# Cont.net
KiCad netlist of a schematic drawn in EAGLE
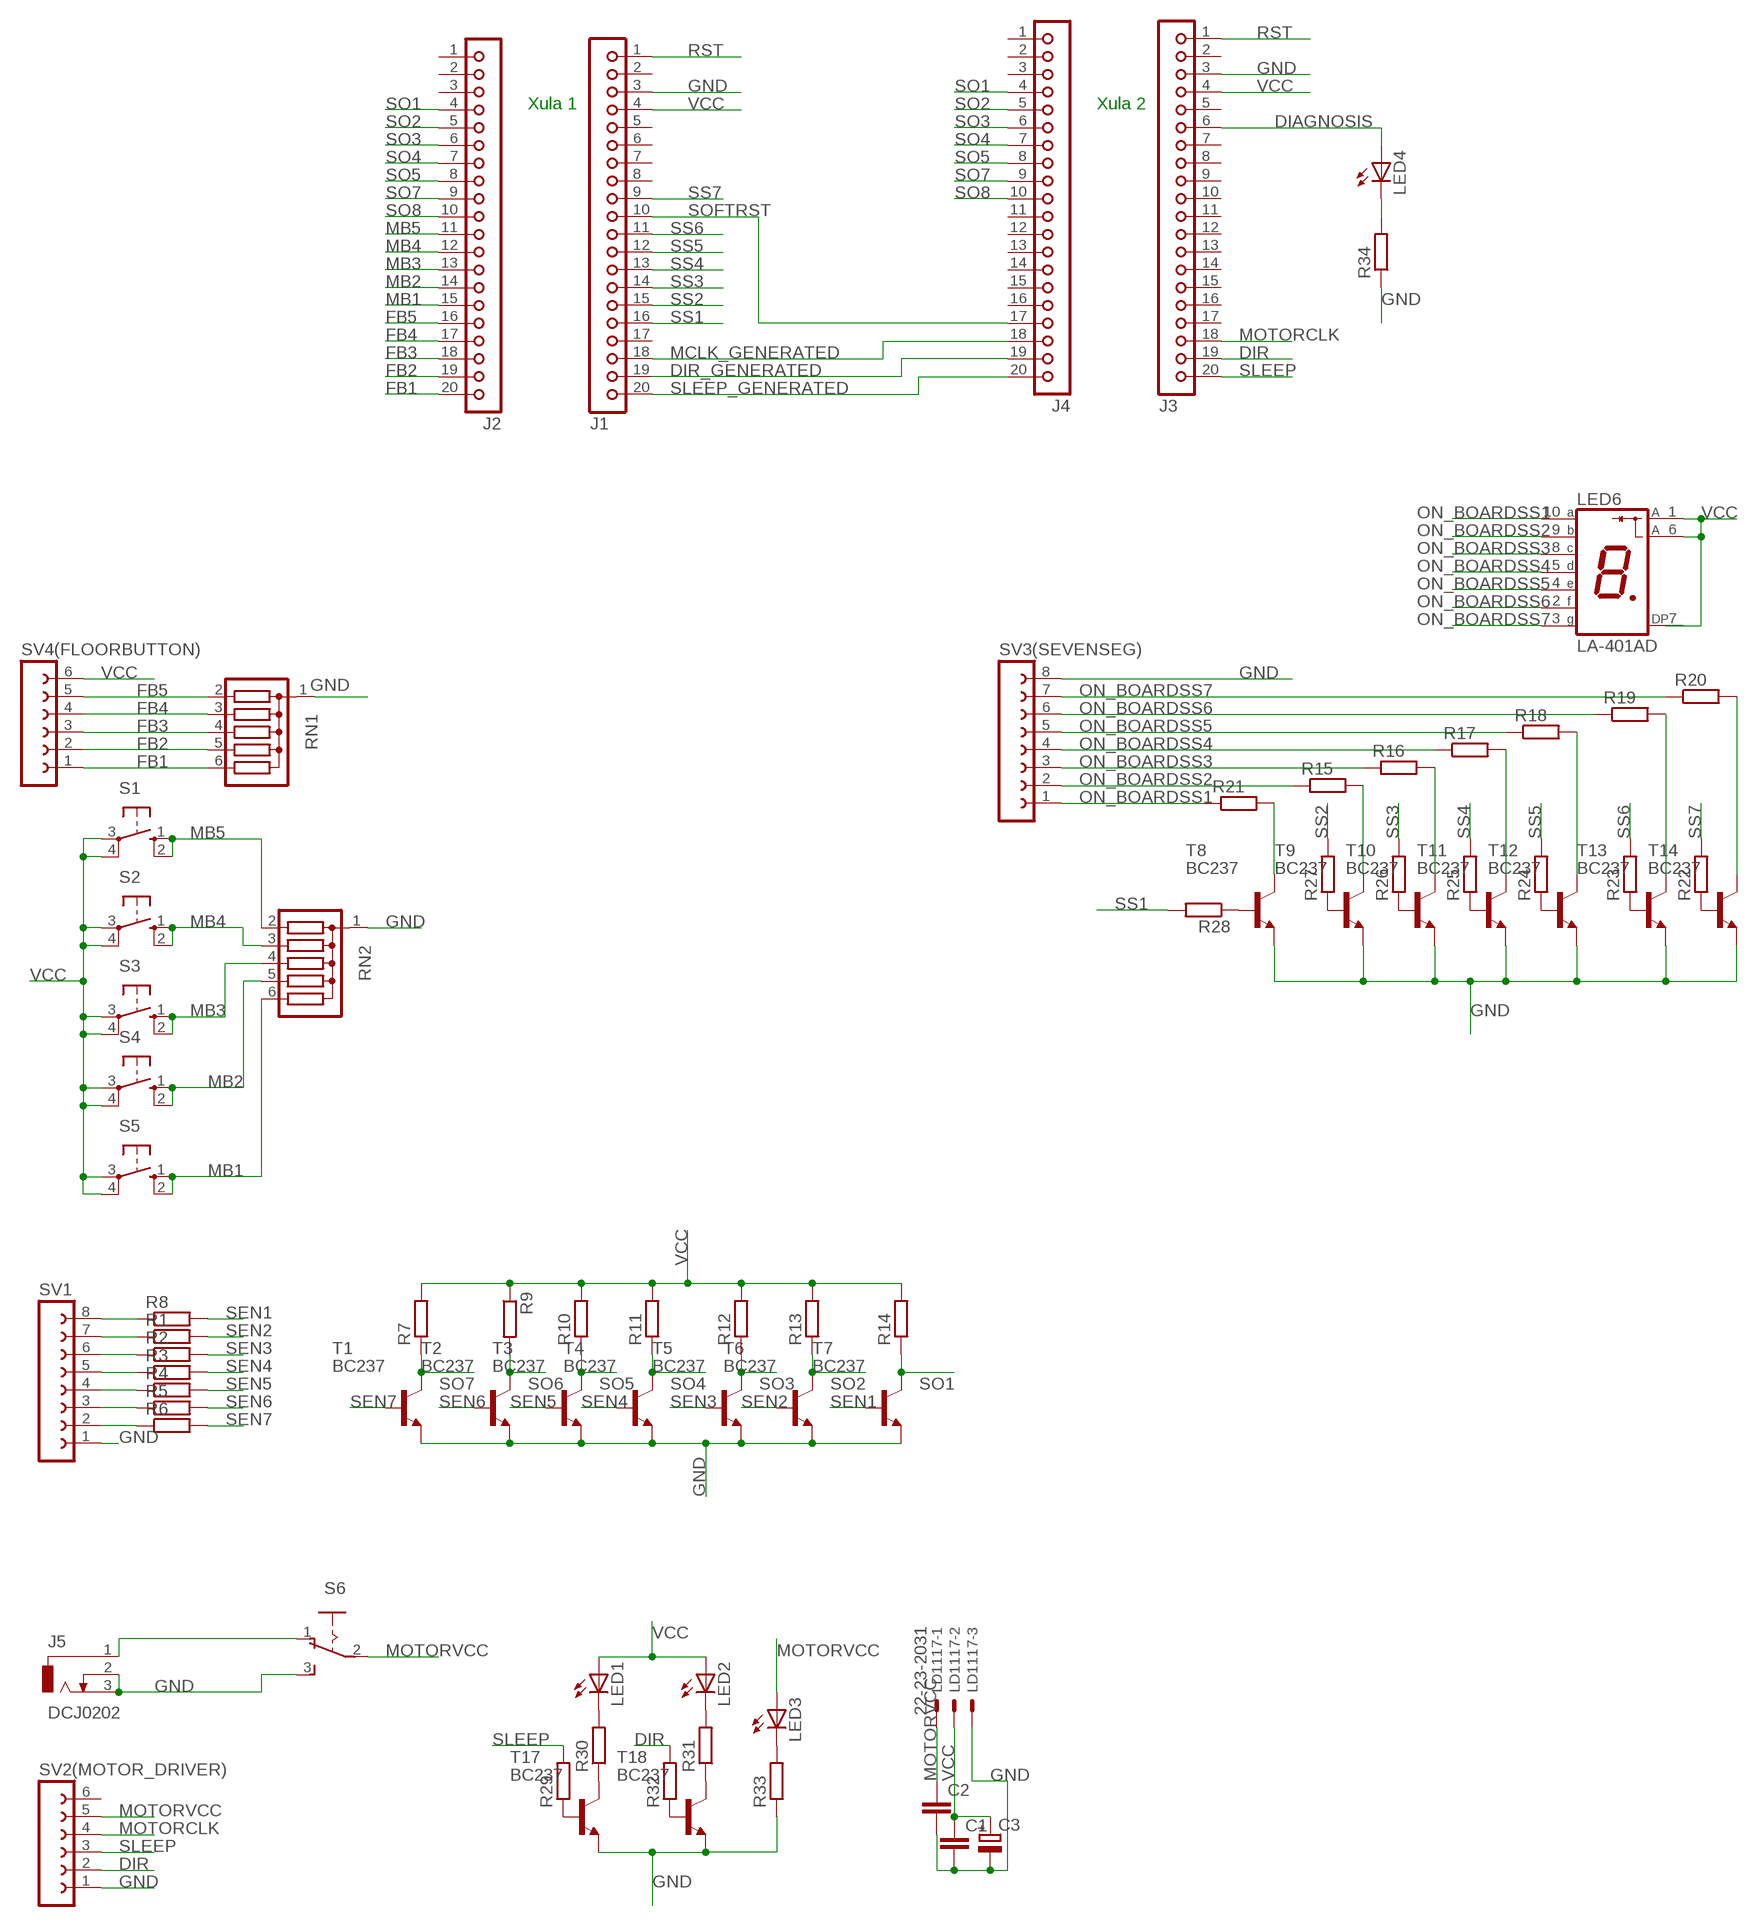
[diagram p0: schematic, sheet 1]

(export (version "E")
  (design (tool "Eeschema 10.0.6"))
  (components
    (comp (ref "C1")
      (value "C-EU025-025X050")
      (footprint "eagle-import:C025-025X050")
      (libsource (lib "eagle-import") (part "C-EU025-025X050"))
    )
    (comp (ref "C2")
      (value "C-EU025-025X050")
      (footprint "eagle-import:C025-025X050")
      (libsource (lib "eagle-import") (part "C-EU025-025X050"))
    )
    (comp (ref "C3")
      (value "CPOL-EUE3.5-8")
      (footprint "eagle-import:E3,5-8")
      (libsource (lib "eagle-import") (part "CPOL-EUE3.5-8"))
    )
    (comp (ref "J1")
      (value "JBK20")
      (footprint "eagle-import:JBK20")
      (libsource (lib "eagle-import") (part "JBK20"))
    )
    (comp (ref "J2")
      (value "JBK20")
      (footprint "eagle-import:JBK20")
      (libsource (lib "eagle-import") (part "JBK20"))
    )
    (comp (ref "J3")
      (value "JBK20")
      (footprint "eagle-import:JBK20")
      (libsource (lib "eagle-import") (part "JBK20"))
    )
    (comp (ref "J4")
      (value "JBK20")
      (footprint "eagle-import:JBK20")
      (libsource (lib "eagle-import") (part "JBK20"))
    )
    (comp (ref "J5")
      (value "DCJ0202")
      (footprint "eagle-import:DCJ0202")
      (libsource (lib "eagle-import") (part "DCJ0202"))
    )
    (comp (ref "LD1117")
      (value "22-23-2031")
      (footprint "eagle-import:22-23-2031")
      (fields (field (name "MF") "MOLEX"))
      (libsource (lib "eagle-import") (part "22-23-2031"))
    )
    (comp (ref "LED1")
      (value "LED3MM")
      (footprint "eagle-import:LED3MM")
      (libsource (lib "eagle-import") (part "LED3MM"))
    )
    (comp (ref "LED2")
      (value "LED3MM")
      (footprint "eagle-import:LED3MM")
      (libsource (lib "eagle-import") (part "LED3MM"))
    )
    (comp (ref "LED3")
      (value "LED3MM")
      (footprint "eagle-import:LED3MM")
      (libsource (lib "eagle-import") (part "LED3MM"))
    )
    (comp (ref "LED4")
      (value "LED3MM")
      (footprint "eagle-import:LED3MM")
      (libsource (lib "eagle-import") (part "LED3MM"))
    )
    (comp (ref "LED6")
      (value "LA-401AD")
      (footprint "eagle-import:LA-401")
      (libsource (lib "eagle-import") (part "LA-401DA"))
    )
    (comp (ref "R1")
      (value "R-EU_0204/5")
      (footprint "eagle-import:0204_5")
      (libsource (lib "eagle-import") (part "R-EU_0204/5"))
    )
    (comp (ref "R2")
      (value "R-EU_0204/5")
      (footprint "eagle-import:0204_5")
      (libsource (lib "eagle-import") (part "R-EU_0204/5"))
    )
    (comp (ref "R3")
      (value "R-EU_0204/5")
      (footprint "eagle-import:0204_5")
      (libsource (lib "eagle-import") (part "R-EU_0204/5"))
    )
    (comp (ref "R4")
      (value "R-EU_0204/5")
      (footprint "eagle-import:0204_5")
      (libsource (lib "eagle-import") (part "R-EU_0204/5"))
    )
    (comp (ref "R5")
      (value "R-EU_0204/5")
      (footprint "eagle-import:0204_5")
      (libsource (lib "eagle-import") (part "R-EU_0204/5"))
    )
    (comp (ref "R6")
      (value "R-EU_0204/5")
      (footprint "eagle-import:0204_5")
      (libsource (lib "eagle-import") (part "R-EU_0204/5"))
    )
    (comp (ref "R7")
      (value "R-EU_0204/5")
      (footprint "eagle-import:0204_5")
      (libsource (lib "eagle-import") (part "R-EU_0204/5"))
    )
    (comp (ref "R8")
      (value "R-EU_0204/5")
      (footprint "eagle-import:0204_5")
      (libsource (lib "eagle-import") (part "R-EU_0204/5"))
    )
    (comp (ref "R9")
      (value "R-EU_0204/5")
      (footprint "eagle-import:0204_5")
      (libsource (lib "eagle-import") (part "R-EU_0204/5"))
    )
    (comp (ref "R10")
      (value "R-EU_0204/5")
      (footprint "eagle-import:0204_5")
      (libsource (lib "eagle-import") (part "R-EU_0204/5"))
    )
    (comp (ref "R11")
      (value "R-EU_0204/5")
      (footprint "eagle-import:0204_5")
      (libsource (lib "eagle-import") (part "R-EU_0204/5"))
    )
    (comp (ref "R12")
      (value "R-EU_0204/5")
      (footprint "eagle-import:0204_5")
      (libsource (lib "eagle-import") (part "R-EU_0204/5"))
    )
    (comp (ref "R13")
      (value "R-EU_0204/5")
      (footprint "eagle-import:0204_5")
      (libsource (lib "eagle-import") (part "R-EU_0204/5"))
    )
    (comp (ref "R14")
      (value "R-EU_0204/5")
      (footprint "eagle-import:0204_5")
      (libsource (lib "eagle-import") (part "R-EU_0204/5"))
    )
    (comp (ref "R15")
      (value "R-EU_0204/5")
      (footprint "eagle-import:0204_5")
      (libsource (lib "eagle-import") (part "R-EU_0204/5"))
    )
    (comp (ref "R16")
      (value "R-EU_0204/5")
      (footprint "eagle-import:0204_5")
      (libsource (lib "eagle-import") (part "R-EU_0204/5"))
    )
    (comp (ref "R17")
      (value "R-EU_0204/5")
      (footprint "eagle-import:0204_5")
      (libsource (lib "eagle-import") (part "R-EU_0204/5"))
    )
    (comp (ref "R18")
      (value "R-EU_0204/5")
      (footprint "eagle-import:0204_5")
      (libsource (lib "eagle-import") (part "R-EU_0204/5"))
    )
    (comp (ref "R19")
      (value "R-EU_0204/5")
      (footprint "eagle-import:0204_5")
      (libsource (lib "eagle-import") (part "R-EU_0204/5"))
    )
    (comp (ref "R20")
      (value "R-EU_0204/5")
      (footprint "eagle-import:0204_5")
      (libsource (lib "eagle-import") (part "R-EU_0204/5"))
    )
    (comp (ref "R21")
      (value "R-EU_0204/5")
      (footprint "eagle-import:0204_5")
      (libsource (lib "eagle-import") (part "R-EU_0204/5"))
    )
    (comp (ref "R22")
      (value "R-EU_0204/5")
      (footprint "eagle-import:0204_5")
      (libsource (lib "eagle-import") (part "R-EU_0204/5"))
    )
    (comp (ref "R23")
      (value "R-EU_0204/5")
      (footprint "eagle-import:0204_5")
      (libsource (lib "eagle-import") (part "R-EU_0204/5"))
    )
    (comp (ref "R24")
      (value "R-EU_0204/5")
      (footprint "eagle-import:0204_5")
      (libsource (lib "eagle-import") (part "R-EU_0204/5"))
    )
    (comp (ref "R25")
      (value "R-EU_0204/5")
      (footprint "eagle-import:0204_5")
      (libsource (lib "eagle-import") (part "R-EU_0204/5"))
    )
    (comp (ref "R26")
      (value "R-EU_0204/5")
      (footprint "eagle-import:0204_5")
      (libsource (lib "eagle-import") (part "R-EU_0204/5"))
    )
    (comp (ref "R27")
      (value "R-EU_0204/5")
      (footprint "eagle-import:0204_5")
      (libsource (lib "eagle-import") (part "R-EU_0204/5"))
    )
    (comp (ref "R28")
      (value "R-EU_0204/5")
      (footprint "eagle-import:0204_5")
      (libsource (lib "eagle-import") (part "R-EU_0204/5"))
    )
    (comp (ref "R29")
      (value "R-EU_0204/5")
      (footprint "eagle-import:0204_5")
      (libsource (lib "eagle-import") (part "R-EU_0204/5"))
    )
    (comp (ref "R30")
      (value "R-EU_0204/5")
      (footprint "eagle-import:0204_5")
      (libsource (lib "eagle-import") (part "R-EU_0204/5"))
    )
    (comp (ref "R31")
      (value "R-EU_0204/5")
      (footprint "eagle-import:0204_5")
      (libsource (lib "eagle-import") (part "R-EU_0204/5"))
    )
    (comp (ref "R32")
      (value "R-EU_0204/5")
      (footprint "eagle-import:0204_5")
      (libsource (lib "eagle-import") (part "R-EU_0204/5"))
    )
    (comp (ref "R33")
      (value "R-EU_0204/5")
      (footprint "eagle-import:0204_5")
      (libsource (lib "eagle-import") (part "R-EU_0204/5"))
    )
    (comp (ref "R34")
      (value "R-EU_0204/5")
      (footprint "eagle-import:0204_5")
      (libsource (lib "eagle-import") (part "R-EU_0204/5"))
    )
    (comp (ref "RN1")
      (value "G05R")
      (footprint "eagle-import:SIL6")
      (libsource (lib "eagle-import") (part "G05R"))
    )
    (comp (ref "RN2")
      (value "G05R")
      (footprint "eagle-import:SIL6")
      (libsource (lib "eagle-import") (part "G05R"))
    )
    (comp (ref "S1")
      (value "10-XX")
      (footprint "eagle-import:B3F-10XX")
      (fields (field (name "MPN") "B3F-1000"))
      (libsource (lib "eagle-import") (part "10-XX"))
    )
    (comp (ref "S2")
      (value "10-XX")
      (footprint "eagle-import:B3F-10XX")
      (fields (field (name "MPN") "B3F-1000"))
      (libsource (lib "eagle-import") (part "10-XX"))
    )
    (comp (ref "S3")
      (value "10-XX")
      (footprint "eagle-import:B3F-10XX")
      (fields (field (name "MPN") "B3F-1000"))
      (libsource (lib "eagle-import") (part "10-XX"))
    )
    (comp (ref "S4")
      (value "10-XX")
      (footprint "eagle-import:B3F-10XX")
      (fields (field (name "MPN") "B3F-1000"))
      (libsource (lib "eagle-import") (part "10-XX"))
    )
    (comp (ref "S5")
      (value "10-XX")
      (footprint "eagle-import:B3F-10XX")
      (fields (field (name "MPN") "B3F-1000"))
      (libsource (lib "eagle-import") (part "10-XX"))
    )
    (comp (ref "S6")
      (value "255SB")
      (footprint "eagle-import:255SB")
      (libsource (lib "eagle-import") (part "255SB"))
    )
    (comp (ref "SV1")
      (value "FE08-1")
      (footprint "eagle-import:FE08")
      (libsource (lib "eagle-import") (part "FE08-1"))
    )
    (comp (ref "SV2(MOTOR_DRIVER)")
      (value "FE06-1")
      (footprint "eagle-import:FE06")
      (libsource (lib "eagle-import") (part "FE06-1"))
    )
    (comp (ref "SV3(SEVENSEG)")
      (value "FE08W")
      (footprint "eagle-import:FE08W")
      (libsource (lib "eagle-import") (part "FE08W"))
    )
    (comp (ref "SV4(FLOORBUTTON)")
      (value "FE06-1")
      (footprint "eagle-import:FE06")
      (libsource (lib "eagle-import") (part "FE06-1"))
    )
    (comp (ref "T1")
      (value "BC237")
      (footprint "eagle-import:TO92")
      (libsource (lib "eagle-import") (part "BC237"))
    )
    (comp (ref "T2")
      (value "BC237")
      (footprint "eagle-import:TO92")
      (libsource (lib "eagle-import") (part "BC237"))
    )
    (comp (ref "T3")
      (value "BC237")
      (footprint "eagle-import:TO92")
      (libsource (lib "eagle-import") (part "BC237"))
    )
    (comp (ref "T4")
      (value "BC237")
      (footprint "eagle-import:TO92")
      (libsource (lib "eagle-import") (part "BC237"))
    )
    (comp (ref "T5")
      (value "BC237")
      (footprint "eagle-import:TO92")
      (libsource (lib "eagle-import") (part "BC237"))
    )
    (comp (ref "T6")
      (value "BC237")
      (footprint "eagle-import:TO92")
      (libsource (lib "eagle-import") (part "BC237"))
    )
    (comp (ref "T7")
      (value "BC237")
      (footprint "eagle-import:TO92")
      (libsource (lib "eagle-import") (part "BC237"))
    )
    (comp (ref "T8")
      (value "BC237")
      (footprint "eagle-import:TO92")
      (libsource (lib "eagle-import") (part "BC237"))
    )
    (comp (ref "T9")
      (value "BC237")
      (footprint "eagle-import:TO92")
      (libsource (lib "eagle-import") (part "BC237"))
    )
    (comp (ref "T10")
      (value "BC237")
      (footprint "eagle-import:TO92")
      (libsource (lib "eagle-import") (part "BC237"))
    )
    (comp (ref "T11")
      (value "BC237")
      (footprint "eagle-import:TO92")
      (libsource (lib "eagle-import") (part "BC237"))
    )
    (comp (ref "T12")
      (value "BC237")
      (footprint "eagle-import:TO92")
      (libsource (lib "eagle-import") (part "BC237"))
    )
    (comp (ref "T13")
      (value "BC237")
      (footprint "eagle-import:TO92")
      (libsource (lib "eagle-import") (part "BC237"))
    )
    (comp (ref "T14")
      (value "BC237")
      (footprint "eagle-import:TO92")
      (libsource (lib "eagle-import") (part "BC237"))
    )
    (comp (ref "T17")
      (value "BC237")
      (footprint "eagle-import:TO92")
      (libsource (lib "eagle-import") (part "BC237"))
    )
    (comp (ref "T18")
      (value "BC237")
      (footprint "eagle-import:TO92")
      (libsource (lib "eagle-import") (part "BC237"))
    )
  )
  (nets
    (net (code "1") (name "/DIAGNOSIS") (class "Default")
      (node (ref "J3") (pin "6") (pinfunction "6_6") (pintype "passive"))
      (node (ref "LED4") (pin "A") (pinfunction "A_A") (pintype "passive"))
    )
    (net (code "2") (name "/DIR") (class "Default")
      (node (ref "J3") (pin "19") (pinfunction "19_19") (pintype "passive"))
      (node (ref "R32") (pin "2") (pinfunction "2_2") (pintype "passive"))
      (node (ref "SV2(MOTOR_DRIVER)") (pin "2") (pinfunction "2_2") (pintype "passive"))
    )
    (net (code "3") (name "/DIR_GENERATED") (class "Default")
      (node (ref "J1") (pin "19") (pinfunction "19_19") (pintype "passive"))
      (node (ref "J4") (pin "19") (pinfunction "19_19") (pintype "passive"))
    )
    (net (code "4") (name "/FB1") (class "Default")
      (node (ref "J2") (pin "20") (pinfunction "20_20") (pintype "passive"))
      (node (ref "RN1") (pin "6") (pinfunction "6_6") (pintype "passive"))
      (node (ref "SV4(FLOORBUTTON)") (pin "1") (pinfunction "1_1") (pintype "passive"))
    )
    (net (code "5") (name "/FB2") (class "Default")
      (node (ref "J2") (pin "19") (pinfunction "19_19") (pintype "passive"))
      (node (ref "RN1") (pin "5") (pinfunction "5_5") (pintype "passive"))
      (node (ref "SV4(FLOORBUTTON)") (pin "2") (pinfunction "2_2") (pintype "passive"))
    )
    (net (code "6") (name "/FB3") (class "Default")
      (node (ref "J2") (pin "18") (pinfunction "18_18") (pintype "passive"))
      (node (ref "RN1") (pin "4") (pinfunction "4_4") (pintype "passive"))
      (node (ref "SV4(FLOORBUTTON)") (pin "3") (pinfunction "3_3") (pintype "passive"))
    )
    (net (code "7") (name "/FB4") (class "Default")
      (node (ref "J2") (pin "17") (pinfunction "17_17") (pintype "passive"))
      (node (ref "RN1") (pin "3") (pinfunction "3_3") (pintype "passive"))
      (node (ref "SV4(FLOORBUTTON)") (pin "4") (pinfunction "4_4") (pintype "passive"))
    )
    (net (code "8") (name "/FB5") (class "Default")
      (node (ref "J2") (pin "16") (pinfunction "16_16") (pintype "passive"))
      (node (ref "RN1") (pin "2") (pinfunction "2_2") (pintype "passive"))
      (node (ref "SV4(FLOORBUTTON)") (pin "5") (pinfunction "5_5") (pintype "passive"))
    )
    (net (code "9") (name "/GND") (class "Default")
      (node (ref "C1") (pin "2") (pinfunction "2_2") (pintype "passive"))
      (node (ref "C2") (pin "2") (pinfunction "2_2") (pintype "passive"))
      (node (ref "C3") (pin "-") (pinfunction "-_-") (pintype "passive"))
      (node (ref "J1") (pin "3") (pinfunction "3_3") (pintype "passive"))
      (node (ref "J3") (pin "3") (pinfunction "3_3") (pintype "passive"))
      (node (ref "J5") (pin "2") (pinfunction "2_2") (pintype "passive"))
      (node (ref "J5") (pin "3") (pinfunction "3_3") (pintype "passive"))
      (node (ref "LD1117") (pin "3") (pinfunction "S_3") (pintype "passive"))
      (node (ref "R33") (pin "1") (pinfunction "1_1") (pintype "passive"))
      (node (ref "R34") (pin "1") (pinfunction "1_1") (pintype "passive"))
      (node (ref "R6") (pin "1") (pinfunction "1_1") (pintype "passive"))
      (node (ref "RN1") (pin "1") (pinfunction "1_1") (pintype "passive"))
      (node (ref "RN2") (pin "1") (pinfunction "1_1") (pintype "passive"))
      (node (ref "S6") (pin "3") (pinfunction "S_3") (pintype "passive"))
      (node (ref "SV1") (pin "1") (pinfunction "1_1") (pintype "passive"))
      (node (ref "SV1") (pin "2") (pinfunction "2_2") (pintype "passive"))
      (node (ref "SV2(MOTOR_DRIVER)") (pin "1") (pinfunction "1_1") (pintype "passive"))
      (node (ref "SV3(SEVENSEG)") (pin "8") (pinfunction "8_8") (pintype "passive"))
      (node (ref "T1") (pin "1") (pinfunction "E_1") (pintype "passive"))
      (node (ref "T10") (pin "1") (pinfunction "E_1") (pintype "passive"))
      (node (ref "T11") (pin "1") (pinfunction "E_1") (pintype "passive"))
      (node (ref "T12") (pin "1") (pinfunction "E_1") (pintype "passive"))
      (node (ref "T13") (pin "1") (pinfunction "E_1") (pintype "passive"))
      (node (ref "T14") (pin "1") (pinfunction "E_1") (pintype "passive"))
      (node (ref "T17") (pin "1") (pinfunction "E_1") (pintype "passive"))
      (node (ref "T18") (pin "1") (pinfunction "E_1") (pintype "passive"))
      (node (ref "T2") (pin "1") (pinfunction "E_1") (pintype "passive"))
      (node (ref "T3") (pin "1") (pinfunction "E_1") (pintype "passive"))
      (node (ref "T4") (pin "1") (pinfunction "E_1") (pintype "passive"))
      (node (ref "T5") (pin "1") (pinfunction "E_1") (pintype "passive"))
      (node (ref "T6") (pin "1") (pinfunction "E_1") (pintype "passive"))
      (node (ref "T7") (pin "1") (pinfunction "E_1") (pintype "passive"))
      (node (ref "T8") (pin "1") (pinfunction "E_1") (pintype "passive"))
      (node (ref "T9") (pin "1") (pinfunction "E_1") (pintype "passive"))
    )
    (net (code "10") (name "/MB1") (class "Default")
      (node (ref "J2") (pin "15") (pinfunction "15_15") (pintype "passive"))
      (node (ref "RN2") (pin "6") (pinfunction "6_6") (pintype "passive"))
      (node (ref "S5") (pin "1") (pinfunction "S_1") (pintype "passive"))
      (node (ref "S5") (pin "2") (pinfunction "S1_2") (pintype "passive"))
    )
    (net (code "11") (name "/MB2") (class "Default")
      (node (ref "J2") (pin "14") (pinfunction "14_14") (pintype "passive"))
      (node (ref "RN2") (pin "5") (pinfunction "5_5") (pintype "passive"))
      (node (ref "S4") (pin "1") (pinfunction "S_1") (pintype "passive"))
      (node (ref "S4") (pin "2") (pinfunction "S1_2") (pintype "passive"))
    )
    (net (code "12") (name "/MB3") (class "Default")
      (node (ref "J2") (pin "13") (pinfunction "13_13") (pintype "passive"))
      (node (ref "RN2") (pin "4") (pinfunction "4_4") (pintype "passive"))
      (node (ref "S3") (pin "1") (pinfunction "S_1") (pintype "passive"))
      (node (ref "S3") (pin "2") (pinfunction "S1_2") (pintype "passive"))
    )
    (net (code "13") (name "/MB4") (class "Default")
      (node (ref "J2") (pin "12") (pinfunction "12_12") (pintype "passive"))
      (node (ref "RN2") (pin "3") (pinfunction "3_3") (pintype "passive"))
      (node (ref "S2") (pin "1") (pinfunction "S_1") (pintype "passive"))
      (node (ref "S2") (pin "2") (pinfunction "S1_2") (pintype "passive"))
    )
    (net (code "14") (name "/MB5") (class "Default")
      (node (ref "J2") (pin "11") (pinfunction "11_11") (pintype "passive"))
      (node (ref "RN2") (pin "2") (pinfunction "2_2") (pintype "passive"))
      (node (ref "S1") (pin "1") (pinfunction "S_1") (pintype "passive"))
      (node (ref "S1") (pin "2") (pinfunction "S1_2") (pintype "passive"))
    )
    (net (code "15") (name "/MCLK_GENERATED") (class "Default")
      (node (ref "J1") (pin "18") (pinfunction "18_18") (pintype "passive"))
      (node (ref "J4") (pin "18") (pinfunction "18_18") (pintype "passive"))
    )
    (net (code "16") (name "/MOTORCLK") (class "Default")
      (node (ref "J3") (pin "18") (pinfunction "18_18") (pintype "passive"))
      (node (ref "SV2(MOTOR_DRIVER)") (pin "4") (pinfunction "4_4") (pintype "passive"))
    )
    (net (code "17") (name "/MOTORVCC") (class "Default")
      (node (ref "C2") (pin "1") (pinfunction "1_1") (pintype "passive"))
      (node (ref "LD1117") (pin "1") (pinfunction "S_1") (pintype "passive"))
      (node (ref "LED3") (pin "A") (pinfunction "A_A") (pintype "passive"))
      (node (ref "S6") (pin "2") (pinfunction "P_2") (pintype "passive"))
      (node (ref "SV2(MOTOR_DRIVER)") (pin "5") (pinfunction "5_5") (pintype "passive"))
    )
    (net (code "18") (name "/ON_BOARDSS1") (class "Default")
      (node (ref "LED6") (pin "10") (pinfunction "A_10") (pintype "passive"))
      (node (ref "R21") (pin "1") (pinfunction "1_1") (pintype "passive"))
      (node (ref "SV3(SEVENSEG)") (pin "1") (pinfunction "1_1") (pintype "passive"))
    )
    (net (code "19") (name "/ON_BOARDSS2") (class "Default")
      (node (ref "LED6") (pin "9") (pinfunction "B_9") (pintype "passive"))
      (node (ref "R15") (pin "1") (pinfunction "1_1") (pintype "passive"))
      (node (ref "SV3(SEVENSEG)") (pin "2") (pinfunction "2_2") (pintype "passive"))
    )
    (net (code "20") (name "/ON_BOARDSS3") (class "Default")
      (node (ref "LED6") (pin "8") (pinfunction "C_8") (pintype "passive"))
      (node (ref "R16") (pin "1") (pinfunction "1_1") (pintype "passive"))
      (node (ref "SV3(SEVENSEG)") (pin "3") (pinfunction "3_3") (pintype "passive"))
    )
    (net (code "21") (name "/ON_BOARDSS4") (class "Default")
      (node (ref "LED6") (pin "5") (pinfunction "D_5") (pintype "passive"))
      (node (ref "R17") (pin "1") (pinfunction "1_1") (pintype "passive"))
      (node (ref "SV3(SEVENSEG)") (pin "4") (pinfunction "4_4") (pintype "passive"))
    )
    (net (code "22") (name "/ON_BOARDSS5") (class "Default")
      (node (ref "LED6") (pin "4") (pinfunction "E_4") (pintype "passive"))
      (node (ref "R18") (pin "1") (pinfunction "1_1") (pintype "passive"))
      (node (ref "SV3(SEVENSEG)") (pin "5") (pinfunction "5_5") (pintype "passive"))
    )
    (net (code "23") (name "/ON_BOARDSS6") (class "Default")
      (node (ref "LED6") (pin "2") (pinfunction "F_2") (pintype "passive"))
      (node (ref "R19") (pin "1") (pinfunction "1_1") (pintype "passive"))
      (node (ref "SV3(SEVENSEG)") (pin "6") (pinfunction "6_6") (pintype "passive"))
    )
    (net (code "24") (name "/ON_BOARDSS7") (class "Default")
      (node (ref "LED6") (pin "3") (pinfunction "G_3") (pintype "passive"))
      (node (ref "R20") (pin "1") (pinfunction "1_1") (pintype "passive"))
      (node (ref "SV3(SEVENSEG)") (pin "7") (pinfunction "7_7") (pintype "passive"))
    )
    (net (code "25") (name "/RST") (class "Default")
      (node (ref "J1") (pin "1") (pinfunction "1_1") (pintype "passive"))
      (node (ref "J3") (pin "1") (pinfunction "1_1") (pintype "passive"))
    )
    (net (code "26") (name "/SEN1") (class "Default")
      (node (ref "R8") (pin "2") (pinfunction "2_2") (pintype "passive"))
      (node (ref "T7") (pin "2") (pinfunction "B_2") (pintype "passive"))
    )
    (net (code "27") (name "/SEN2") (class "Default")
      (node (ref "R1") (pin "2") (pinfunction "2_2") (pintype "passive"))
      (node (ref "T6") (pin "2") (pinfunction "B_2") (pintype "passive"))
    )
    (net (code "28") (name "/SEN3") (class "Default")
      (node (ref "R2") (pin "2") (pinfunction "2_2") (pintype "passive"))
      (node (ref "T5") (pin "2") (pinfunction "B_2") (pintype "passive"))
    )
    (net (code "29") (name "/SEN4") (class "Default")
      (node (ref "R3") (pin "2") (pinfunction "2_2") (pintype "passive"))
      (node (ref "T4") (pin "2") (pinfunction "B_2") (pintype "passive"))
    )
    (net (code "30") (name "/SEN5") (class "Default")
      (node (ref "R4") (pin "2") (pinfunction "2_2") (pintype "passive"))
      (node (ref "T3") (pin "2") (pinfunction "B_2") (pintype "passive"))
    )
    (net (code "31") (name "/SEN6") (class "Default")
      (node (ref "R5") (pin "2") (pinfunction "2_2") (pintype "passive"))
      (node (ref "T2") (pin "2") (pinfunction "B_2") (pintype "passive"))
    )
    (net (code "32") (name "/SEN7") (class "Default")
      (node (ref "R6") (pin "2") (pinfunction "2_2") (pintype "passive"))
      (node (ref "T1") (pin "2") (pinfunction "B_2") (pintype "passive"))
    )
    (net (code "33") (name "/SLEEP") (class "Default")
      (node (ref "J3") (pin "20") (pinfunction "20_20") (pintype "passive"))
      (node (ref "R29") (pin "2") (pinfunction "2_2") (pintype "passive"))
      (node (ref "SV2(MOTOR_DRIVER)") (pin "3") (pinfunction "3_3") (pintype "passive"))
    )
    (net (code "34") (name "/SLEEP_GENERATED") (class "Default")
      (node (ref "J1") (pin "20") (pinfunction "20_20") (pintype "passive"))
      (node (ref "J4") (pin "20") (pinfunction "20_20") (pintype "passive"))
    )
    (net (code "35") (name "/SO1") (class "Default")
      (node (ref "J2") (pin "4") (pinfunction "4_4") (pintype "passive"))
      (node (ref "J4") (pin "4") (pinfunction "4_4") (pintype "passive"))
      (node (ref "R14") (pin "1") (pinfunction "1_1") (pintype "passive"))
      (node (ref "T7") (pin "3") (pinfunction "C_3") (pintype "passive"))
    )
    (net (code "36") (name "/SO2") (class "Default")
      (node (ref "J2") (pin "5") (pinfunction "5_5") (pintype "passive"))
      (node (ref "J4") (pin "5") (pinfunction "5_5") (pintype "passive"))
      (node (ref "R13") (pin "1") (pinfunction "1_1") (pintype "passive"))
      (node (ref "T6") (pin "3") (pinfunction "C_3") (pintype "passive"))
    )
    (net (code "37") (name "/SO3") (class "Default")
      (node (ref "J2") (pin "6") (pinfunction "6_6") (pintype "passive"))
      (node (ref "J4") (pin "6") (pinfunction "6_6") (pintype "passive"))
      (node (ref "R12") (pin "1") (pinfunction "1_1") (pintype "passive"))
      (node (ref "T5") (pin "3") (pinfunction "C_3") (pintype "passive"))
    )
    (net (code "38") (name "/SO4") (class "Default")
      (node (ref "J2") (pin "7") (pinfunction "7_7") (pintype "passive"))
      (node (ref "J4") (pin "7") (pinfunction "7_7") (pintype "passive"))
      (node (ref "R11") (pin "1") (pinfunction "1_1") (pintype "passive"))
      (node (ref "T4") (pin "3") (pinfunction "C_3") (pintype "passive"))
    )
    (net (code "39") (name "/SO5") (class "Default")
      (node (ref "J2") (pin "8") (pinfunction "8_8") (pintype "passive"))
      (node (ref "J4") (pin "8") (pinfunction "8_8") (pintype "passive"))
      (node (ref "R10") (pin "1") (pinfunction "1_1") (pintype "passive"))
      (node (ref "T3") (pin "3") (pinfunction "C_3") (pintype "passive"))
    )
    (net (code "40") (name "/SO6") (class "Default")
      (node (ref "R9") (pin "2") (pinfunction "2_2") (pintype "passive"))
      (node (ref "T2") (pin "3") (pinfunction "C_3") (pintype "passive"))
    )
    (net (code "41") (name "/SO7") (class "Default")
      (node (ref "J2") (pin "9") (pinfunction "9_9") (pintype "passive"))
      (node (ref "J4") (pin "9") (pinfunction "9_9") (pintype "passive"))
      (node (ref "R7") (pin "1") (pinfunction "1_1") (pintype "passive"))
      (node (ref "T1") (pin "3") (pinfunction "C_3") (pintype "passive"))
    )
    (net (code "42") (name "/SO8") (class "Default")
      (node (ref "J2") (pin "10") (pinfunction "10_10") (pintype "passive"))
      (node (ref "J4") (pin "10") (pinfunction "10_10") (pintype "passive"))
    )
    (net (code "43") (name "/SOFTRST") (class "Default")
      (node (ref "J1") (pin "10") (pinfunction "10_10") (pintype "passive"))
      (node (ref "J4") (pin "17") (pinfunction "17_17") (pintype "passive"))
    )
    (net (code "44") (name "/SS1") (class "Default")
      (node (ref "J1") (pin "16") (pinfunction "16_16") (pintype "passive"))
      (node (ref "R28") (pin "2") (pinfunction "2_2") (pintype "passive"))
    )
    (net (code "45") (name "/SS2") (class "Default")
      (node (ref "J1") (pin "15") (pinfunction "15_15") (pintype "passive"))
      (node (ref "R27") (pin "2") (pinfunction "2_2") (pintype "passive"))
    )
    (net (code "46") (name "/SS3") (class "Default")
      (node (ref "J1") (pin "14") (pinfunction "14_14") (pintype "passive"))
      (node (ref "R26") (pin "2") (pinfunction "2_2") (pintype "passive"))
    )
    (net (code "47") (name "/SS4") (class "Default")
      (node (ref "J1") (pin "13") (pinfunction "13_13") (pintype "passive"))
      (node (ref "R25") (pin "2") (pinfunction "2_2") (pintype "passive"))
    )
    (net (code "48") (name "/SS5") (class "Default")
      (node (ref "J1") (pin "12") (pinfunction "12_12") (pintype "passive"))
      (node (ref "R24") (pin "2") (pinfunction "2_2") (pintype "passive"))
    )
    (net (code "49") (name "/SS6") (class "Default")
      (node (ref "J1") (pin "11") (pinfunction "11_11") (pintype "passive"))
      (node (ref "R23") (pin "2") (pinfunction "2_2") (pintype "passive"))
    )
    (net (code "50") (name "/SS7") (class "Default")
      (node (ref "J1") (pin "9") (pinfunction "9_9") (pintype "passive"))
      (node (ref "R22") (pin "2") (pinfunction "2_2") (pintype "passive"))
    )
    (net (code "51") (name "/VCC") (class "Default")
      (node (ref "C1") (pin "1") (pinfunction "1_1") (pintype "passive"))
      (node (ref "C3") (pin "+") (pinfunction "+_+") (pintype "passive"))
      (node (ref "J1") (pin "4") (pinfunction "4_4") (pintype "passive"))
      (node (ref "J3") (pin "4") (pinfunction "4_4") (pintype "passive"))
      (node (ref "LD1117") (pin "2") (pinfunction "S_2") (pintype "passive"))
      (node (ref "LED1") (pin "A") (pinfunction "A_A") (pintype "passive"))
      (node (ref "LED2") (pin "A") (pinfunction "A_A") (pintype "passive"))
      (node (ref "LED6") (pin "1") (pinfunction "A_1") (pintype "passive"))
      (node (ref "LED6") (pin "6") (pinfunction "A_6") (pintype "passive"))
      (node (ref "R10") (pin "2") (pinfunction "2_2") (pintype "passive"))
      (node (ref "R11") (pin "2") (pinfunction "2_2") (pintype "passive"))
      (node (ref "R12") (pin "2") (pinfunction "2_2") (pintype "passive"))
      (node (ref "R13") (pin "2") (pinfunction "2_2") (pintype "passive"))
      (node (ref "R14") (pin "2") (pinfunction "2_2") (pintype "passive"))
      (node (ref "R7") (pin "2") (pinfunction "2_2") (pintype "passive"))
      (node (ref "R9") (pin "1") (pinfunction "1_1") (pintype "passive"))
      (node (ref "S1") (pin "3") (pinfunction "P_3") (pintype "passive"))
      (node (ref "S1") (pin "4") (pinfunction "P1_4") (pintype "passive"))
      (node (ref "S2") (pin "3") (pinfunction "P_3") (pintype "passive"))
      (node (ref "S2") (pin "4") (pinfunction "P1_4") (pintype "passive"))
      (node (ref "S3") (pin "3") (pinfunction "P_3") (pintype "passive"))
      (node (ref "S3") (pin "4") (pinfunction "P1_4") (pintype "passive"))
      (node (ref "S4") (pin "3") (pinfunction "P_3") (pintype "passive"))
      (node (ref "S4") (pin "4") (pinfunction "P1_4") (pintype "passive"))
      (node (ref "S5") (pin "3") (pinfunction "P_3") (pintype "passive"))
      (node (ref "S5") (pin "4") (pinfunction "P1_4") (pintype "passive"))
      (node (ref "SV4(FLOORBUTTON)") (pin "6") (pinfunction "6_6") (pintype "passive"))
    )
    (net (code "52") (name "Net-(LED1-C)") (class "Default")
      (node (ref "LED1") (pin "K") (pinfunction "C_K") (pintype "passive"))
      (node (ref "R30") (pin "2") (pinfunction "2_2") (pintype "passive"))
    )
    (net (code "53") (name "Net-(LED2-C)") (class "Default")
      (node (ref "LED2") (pin "K") (pinfunction "C_K") (pintype "passive"))
      (node (ref "R31") (pin "2") (pinfunction "2_2") (pintype "passive"))
    )
    (net (code "54") (name "Net-(LED3-C)") (class "Default")
      (node (ref "LED3") (pin "K") (pinfunction "C_K") (pintype "passive"))
      (node (ref "R33") (pin "2") (pinfunction "2_2") (pintype "passive"))
    )
    (net (code "55") (name "Net-(LED4-C)") (class "Default")
      (node (ref "LED4") (pin "K") (pinfunction "C_K") (pintype "passive"))
      (node (ref "R34") (pin "2") (pinfunction "2_2") (pintype "passive"))
    )
    (net (code "56") (name "Net-(R1-Pad1)") (class "Default")
      (node (ref "R1") (pin "1") (pinfunction "1_1") (pintype "passive"))
      (node (ref "SV1") (pin "7") (pinfunction "7_7") (pintype "passive"))
    )
    (net (code "57") (name "Net-(R2-Pad1)") (class "Default")
      (node (ref "R2") (pin "1") (pinfunction "1_1") (pintype "passive"))
      (node (ref "SV1") (pin "6") (pinfunction "6_6") (pintype "passive"))
    )
    (net (code "58") (name "Net-(R3-Pad1)") (class "Default")
      (node (ref "R3") (pin "1") (pinfunction "1_1") (pintype "passive"))
      (node (ref "SV1") (pin "5") (pinfunction "5_5") (pintype "passive"))
    )
    (net (code "59") (name "Net-(R4-Pad1)") (class "Default")
      (node (ref "R4") (pin "1") (pinfunction "1_1") (pintype "passive"))
      (node (ref "SV1") (pin "4") (pinfunction "4_4") (pintype "passive"))
    )
    (net (code "60") (name "Net-(R5-Pad1)") (class "Default")
      (node (ref "R5") (pin "1") (pinfunction "1_1") (pintype "passive"))
      (node (ref "SV1") (pin "3") (pinfunction "3_3") (pintype "passive"))
    )
    (net (code "61") (name "Net-(R8-Pad1)") (class "Default")
      (node (ref "R8") (pin "1") (pinfunction "1_1") (pintype "passive"))
      (node (ref "SV1") (pin "8") (pinfunction "8_8") (pintype "passive"))
    )
    (net (code "62") (name "Net-(S6-O)") (class "Default")
      (node (ref "J5") (pin "1") (pinfunction "1_1") (pintype "passive"))
      (node (ref "S6") (pin "1") (pinfunction "O_1") (pintype "passive"))
    )
    (net (code "63") (name "Net-(T8-B)") (class "Default")
      (node (ref "R28") (pin "1") (pinfunction "1_1") (pintype "passive"))
      (node (ref "T8") (pin "2") (pinfunction "B_2") (pintype "passive"))
    )
    (net (code "64") (name "Net-(T8-C)") (class "Default")
      (node (ref "R21") (pin "2") (pinfunction "2_2") (pintype "passive"))
      (node (ref "T8") (pin "3") (pinfunction "C_3") (pintype "passive"))
    )
    (net (code "65") (name "Net-(T9-B)") (class "Default")
      (node (ref "R27") (pin "1") (pinfunction "1_1") (pintype "passive"))
      (node (ref "T9") (pin "2") (pinfunction "B_2") (pintype "passive"))
    )
    (net (code "66") (name "Net-(T9-C)") (class "Default")
      (node (ref "R15") (pin "2") (pinfunction "2_2") (pintype "passive"))
      (node (ref "T9") (pin "3") (pinfunction "C_3") (pintype "passive"))
    )
    (net (code "67") (name "Net-(T10-B)") (class "Default")
      (node (ref "R26") (pin "1") (pinfunction "1_1") (pintype "passive"))
      (node (ref "T10") (pin "2") (pinfunction "B_2") (pintype "passive"))
    )
    (net (code "68") (name "Net-(T10-C)") (class "Default")
      (node (ref "R16") (pin "2") (pinfunction "2_2") (pintype "passive"))
      (node (ref "T10") (pin "3") (pinfunction "C_3") (pintype "passive"))
    )
    (net (code "69") (name "Net-(T11-B)") (class "Default")
      (node (ref "R25") (pin "1") (pinfunction "1_1") (pintype "passive"))
      (node (ref "T11") (pin "2") (pinfunction "B_2") (pintype "passive"))
    )
    (net (code "70") (name "Net-(T11-C)") (class "Default")
      (node (ref "R17") (pin "2") (pinfunction "2_2") (pintype "passive"))
      (node (ref "T11") (pin "3") (pinfunction "C_3") (pintype "passive"))
    )
    (net (code "71") (name "Net-(T12-B)") (class "Default")
      (node (ref "R24") (pin "1") (pinfunction "1_1") (pintype "passive"))
      (node (ref "T12") (pin "2") (pinfunction "B_2") (pintype "passive"))
    )
    (net (code "72") (name "Net-(T12-C)") (class "Default")
      (node (ref "R18") (pin "2") (pinfunction "2_2") (pintype "passive"))
      (node (ref "T12") (pin "3") (pinfunction "C_3") (pintype "passive"))
    )
    (net (code "73") (name "Net-(T13-B)") (class "Default")
      (node (ref "R23") (pin "1") (pinfunction "1_1") (pintype "passive"))
      (node (ref "T13") (pin "2") (pinfunction "B_2") (pintype "passive"))
    )
    (net (code "74") (name "Net-(T13-C)") (class "Default")
      (node (ref "R19") (pin "2") (pinfunction "2_2") (pintype "passive"))
      (node (ref "T13") (pin "3") (pinfunction "C_3") (pintype "passive"))
    )
    (net (code "75") (name "Net-(T14-B)") (class "Default")
      (node (ref "R22") (pin "1") (pinfunction "1_1") (pintype "passive"))
      (node (ref "T14") (pin "2") (pinfunction "B_2") (pintype "passive"))
    )
    (net (code "76") (name "Net-(T14-C)") (class "Default")
      (node (ref "R20") (pin "2") (pinfunction "2_2") (pintype "passive"))
      (node (ref "T14") (pin "3") (pinfunction "C_3") (pintype "passive"))
    )
    (net (code "77") (name "Net-(T17-B)") (class "Default")
      (node (ref "R29") (pin "1") (pinfunction "1_1") (pintype "passive"))
      (node (ref "T17") (pin "2") (pinfunction "B_2") (pintype "passive"))
    )
    (net (code "78") (name "Net-(T17-C)") (class "Default")
      (node (ref "R30") (pin "1") (pinfunction "1_1") (pintype "passive"))
      (node (ref "T17") (pin "3") (pinfunction "C_3") (pintype "passive"))
    )
    (net (code "79") (name "Net-(T18-B)") (class "Default")
      (node (ref "R32") (pin "1") (pinfunction "1_1") (pintype "passive"))
      (node (ref "T18") (pin "2") (pinfunction "B_2") (pintype "passive"))
    )
    (net (code "80") (name "Net-(T18-C)") (class "Default")
      (node (ref "R31") (pin "1") (pinfunction "1_1") (pintype "passive"))
      (node (ref "T18") (pin "3") (pinfunction "C_3") (pintype "passive"))
    )
    (net (code "81") (name "unconnected-(J1-Pad2)") (class "Default")
      (node (ref "J1") (pin "2") (pinfunction "2_2") (pintype "passive"))
    )
    (net (code "82") (name "unconnected-(J1-Pad5)") (class "Default")
      (node (ref "J1") (pin "5") (pinfunction "5_5") (pintype "passive"))
    )
    (net (code "83") (name "unconnected-(J1-Pad6)") (class "Default")
      (node (ref "J1") (pin "6") (pinfunction "6_6") (pintype "passive"))
    )
    (net (code "84") (name "unconnected-(J1-Pad7)") (class "Default")
      (node (ref "J1") (pin "7") (pinfunction "7_7") (pintype "passive"))
    )
    (net (code "85") (name "unconnected-(J1-Pad8)") (class "Default")
      (node (ref "J1") (pin "8") (pinfunction "8_8") (pintype "passive"))
    )
    (net (code "86") (name "unconnected-(J1-Pad17)") (class "Default")
      (node (ref "J1") (pin "17") (pinfunction "17_17") (pintype "passive"))
    )
    (net (code "87") (name "unconnected-(J2-Pad1)") (class "Default")
      (node (ref "J2") (pin "1") (pinfunction "1_1") (pintype "passive"))
    )
    (net (code "88") (name "unconnected-(J2-Pad2)") (class "Default")
      (node (ref "J2") (pin "2") (pinfunction "2_2") (pintype "passive"))
    )
    (net (code "89") (name "unconnected-(J2-Pad3)") (class "Default")
      (node (ref "J2") (pin "3") (pinfunction "3_3") (pintype "passive"))
    )
    (net (code "90") (name "unconnected-(J3-Pad2)") (class "Default")
      (node (ref "J3") (pin "2") (pinfunction "2_2") (pintype "passive"))
    )
    (net (code "91") (name "unconnected-(J3-Pad5)") (class "Default")
      (node (ref "J3") (pin "5") (pinfunction "5_5") (pintype "passive"))
    )
    (net (code "92") (name "unconnected-(J3-Pad7)") (class "Default")
      (node (ref "J3") (pin "7") (pinfunction "7_7") (pintype "passive"))
    )
    (net (code "93") (name "unconnected-(J3-Pad8)") (class "Default")
      (node (ref "J3") (pin "8") (pinfunction "8_8") (pintype "passive"))
    )
    (net (code "94") (name "unconnected-(J3-Pad9)") (class "Default")
      (node (ref "J3") (pin "9") (pinfunction "9_9") (pintype "passive"))
    )
    (net (code "95") (name "unconnected-(J3-Pad10)") (class "Default")
      (node (ref "J3") (pin "10") (pinfunction "10_10") (pintype "passive"))
    )
    (net (code "96") (name "unconnected-(J3-Pad11)") (class "Default")
      (node (ref "J3") (pin "11") (pinfunction "11_11") (pintype "passive"))
    )
    (net (code "97") (name "unconnected-(J3-Pad12)") (class "Default")
      (node (ref "J3") (pin "12") (pinfunction "12_12") (pintype "passive"))
    )
    (net (code "98") (name "unconnected-(J3-Pad13)") (class "Default")
      (node (ref "J3") (pin "13") (pinfunction "13_13") (pintype "passive"))
    )
    (net (code "99") (name "unconnected-(J3-Pad14)") (class "Default")
      (node (ref "J3") (pin "14") (pinfunction "14_14") (pintype "passive"))
    )
    (net (code "100") (name "unconnected-(J3-Pad15)") (class "Default")
      (node (ref "J3") (pin "15") (pinfunction "15_15") (pintype "passive"))
    )
    (net (code "101") (name "unconnected-(J3-Pad16)") (class "Default")
      (node (ref "J3") (pin "16") (pinfunction "16_16") (pintype "passive"))
    )
    (net (code "102") (name "unconnected-(J3-Pad17)") (class "Default")
      (node (ref "J3") (pin "17") (pinfunction "17_17") (pintype "passive"))
    )
    (net (code "103") (name "unconnected-(J4-Pad1)") (class "Default")
      (node (ref "J4") (pin "1") (pinfunction "1_1") (pintype "passive"))
    )
    (net (code "104") (name "unconnected-(J4-Pad2)") (class "Default")
      (node (ref "J4") (pin "2") (pinfunction "2_2") (pintype "passive"))
    )
    (net (code "105") (name "unconnected-(J4-Pad3)") (class "Default")
      (node (ref "J4") (pin "3") (pinfunction "3_3") (pintype "passive"))
    )
    (net (code "106") (name "unconnected-(J4-Pad11)") (class "Default")
      (node (ref "J4") (pin "11") (pinfunction "11_11") (pintype "passive"))
    )
    (net (code "107") (name "unconnected-(J4-Pad12)") (class "Default")
      (node (ref "J4") (pin "12") (pinfunction "12_12") (pintype "passive"))
    )
    (net (code "108") (name "unconnected-(J4-Pad13)") (class "Default")
      (node (ref "J4") (pin "13") (pinfunction "13_13") (pintype "passive"))
    )
    (net (code "109") (name "unconnected-(J4-Pad14)") (class "Default")
      (node (ref "J4") (pin "14") (pinfunction "14_14") (pintype "passive"))
    )
    (net (code "110") (name "unconnected-(J4-Pad15)") (class "Default")
      (node (ref "J4") (pin "15") (pinfunction "15_15") (pintype "passive"))
    )
    (net (code "111") (name "unconnected-(J4-Pad16)") (class "Default")
      (node (ref "J4") (pin "16") (pinfunction "16_16") (pintype "passive"))
    )
    (net (code "112") (name "unconnected-(LED6-DP-Pad7)") (class "Default")
      (node (ref "LED6") (pin "7") (pinfunction "DP_7") (pintype "passive"))
    )
    (net (code "113") (name "unconnected-(SV2(MOTOR_DRIVER)-Pad6)") (class "Default")
      (node (ref "SV2(MOTOR_DRIVER)") (pin "6") (pinfunction "6_6") (pintype "passive"))
    )
  )
)
